# Alternate_power.net
KiCad netlist of a schematic drawn in Altium Designer
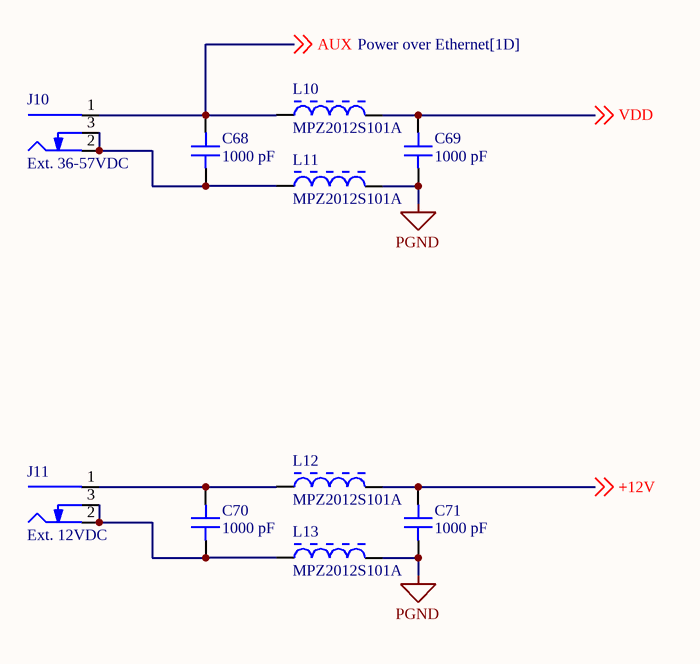
[diagram p0: Alternate power.SchDoc]

(export (version "E")
  (design (tool "Eeschema 10.0.6"))
  (components
    (comp (ref "C68")
      (value "1000 pF")
      (footprint "CAP 0603_1608")
      (description "CAP CER 1000PF 100V X7R 0603")
      (fields
        (field (name "PART NUMBER") "C1608X7R2A102K080AA")
        (field (name "CAPACITANCE") "1000 pF")
        (field (name "MANUFACTURER") "TDK Corporation")
      )
      (libsource (lib "Celestial Altium Library - altium_library") (part "Capacitor"))
    )
    (comp (ref "C69")
      (value "1000 pF")
      (footprint "CAP 0603_1608")
      (description "CAP CER 1000PF 100V X7R 0603")
      (fields
        (field (name "PART NUMBER") "C1608X7R2A102K080AA")
        (field (name "CAPACITANCE") "1000 pF")
        (field (name "MANUFACTURER") "TDK Corporation")
      )
      (libsource (lib "Celestial Altium Library - altium_library") (part "Capacitor"))
    )
    (comp (ref "C70")
      (value "1000 pF")
      (footprint "CAP 0603_1608")
      (description "CAP CER 1000PF 100V X7R 0603")
      (fields
        (field (name "PART NUMBER") "C1608X7R2A102K080AA")
        (field (name "CAPACITANCE") "1000 pF")
        (field (name "MANUFACTURER") "TDK Corporation")
      )
      (libsource (lib "Celestial Altium Library - altium_library") (part "Capacitor"))
    )
    (comp (ref "C71")
      (value "1000 pF")
      (footprint "CAP 0603_1608")
      (description "CAP CER 1000PF 100V X7R 0603")
      (fields
        (field (name "PART NUMBER") "C1608X7R2A102K080AA")
        (field (name "CAPACITANCE") "1000 pF")
        (field (name "MANUFACTURER") "TDK Corporation")
      )
      (libsource (lib "Celestial Altium Library - altium_library") (part "Capacitor"))
    )
    (comp (ref "J10")
      (value "Ext. 36-57VDC")
      (footprint "CUI PJ-002AH-SMT-TR")
      (description "CONN PWR JACK 2X5.5MM SOLDER")
      (fields (field (name "PART NUMBER") "PJ-002AH-SMT-TR") (field (name "MANUFACTURER") "CUI Devices"))
      (libsource (lib "Celestial Altium Library - altium_library") (part "Barrel Connector"))
    )
    (comp (ref "J11")
      (value "Ext. 12VDC")
      (footprint "CUI PJ-002AH-SMT-TR")
      (description "CONN PWR JACK 2X5.5MM SOLDER")
      (fields (field (name "PART NUMBER") "PJ-002AH-SMT-TR") (field (name "MANUFACTURER") "CUI Devices"))
      (libsource (lib "Celestial Altium Library - altium_library") (part "Barrel Connector"))
    )
    (comp (ref "L10")
      (value "MPZ2012S101A")
      (footprint "TDK-MPZ2012S101A-2_V")
      (fields (field (name "TOLERANCE") "25%") (field (name "MANUFACTURER") "TDK"))
      (libsource (lib "Altium Content Vault") (part "BEAD-2"))
    )
    (comp (ref "L11")
      (value "MPZ2012S101A")
      (footprint "TDK-MPZ2012S101A-2_V")
      (fields (field (name "TOLERANCE") "25%") (field (name "MANUFACTURER") "TDK"))
      (libsource (lib "Altium Content Vault") (part "BEAD-2"))
    )
    (comp (ref "L12")
      (value "MPZ2012S101A")
      (footprint "TDK-MPZ2012S101A-2_V")
      (fields (field (name "TOLERANCE") "25%") (field (name "MANUFACTURER") "TDK"))
      (libsource (lib "Altium Content Vault") (part "BEAD-2"))
    )
    (comp (ref "L13")
      (value "MPZ2012S101A")
      (footprint "TDK-MPZ2012S101A-2_V")
      (fields (field (name "TOLERANCE") "25%") (field (name "MANUFACTURER") "TDK"))
      (libsource (lib "Altium Content Vault") (part "BEAD-2"))
    )
  )
  (nets
    (net (code "1") (name "+12V") (class "Default")
      (node (ref "C71") (pin "2") (pinfunction "2_2") (pintype "passive"))
      (node (ref "L12") (pin "2") (pinfunction "2_2") (pintype "passive"))
    )
    (net (code "2") (name "AUX") (class "Default")
      (node (ref "C68") (pin "2") (pinfunction "2_2") (pintype "passive"))
      (node (ref "J10") (pin "1") (pinfunction "Centre_1") (pintype "passive"))
      (node (ref "L10") (pin "1") (pinfunction "1_1") (pintype "passive"))
    )
    (net (code "3") (name "Net-(J10-Outer)") (class "Default")
      (node (ref "C68") (pin "1") (pinfunction "1_1") (pintype "passive"))
      (node (ref "J10") (pin "2") (pinfunction "Outer_2") (pintype "passive"))
      (node (ref "J10") (pin "3") (pinfunction "SW_3") (pintype "passive"))
      (node (ref "L11") (pin "1") (pinfunction "1_1") (pintype "passive"))
    )
    (net (code "4") (name "Net-(J11-Centre)") (class "Default")
      (node (ref "C70") (pin "2") (pinfunction "2_2") (pintype "passive"))
      (node (ref "J11") (pin "1") (pinfunction "Centre_1") (pintype "passive"))
      (node (ref "L12") (pin "1") (pinfunction "1_1") (pintype "passive"))
    )
    (net (code "5") (name "Net-(J11-Outer)") (class "Default")
      (node (ref "C70") (pin "1") (pinfunction "1_1") (pintype "passive"))
      (node (ref "J11") (pin "2") (pinfunction "Outer_2") (pintype "passive"))
      (node (ref "J11") (pin "3") (pinfunction "SW_3") (pintype "passive"))
      (node (ref "L13") (pin "1") (pinfunction "1_1") (pintype "passive"))
    )
    (net (code "6") (name "PGND") (class "Default")
      (node (ref "C69") (pin "1") (pinfunction "1_1") (pintype "passive"))
      (node (ref "C71") (pin "1") (pinfunction "1_1") (pintype "passive"))
      (node (ref "L11") (pin "2") (pinfunction "2_2") (pintype "passive"))
      (node (ref "L13") (pin "2") (pinfunction "2_2") (pintype "passive"))
    )
    (net (code "7") (name "VDD") (class "Default")
      (node (ref "C69") (pin "2") (pinfunction "2_2") (pintype "passive"))
      (node (ref "L10") (pin "2") (pinfunction "2_2") (pintype "passive"))
    )
  )
)
